# External_Connectors.net
KiCad netlist of a schematic drawn in Altium Designer
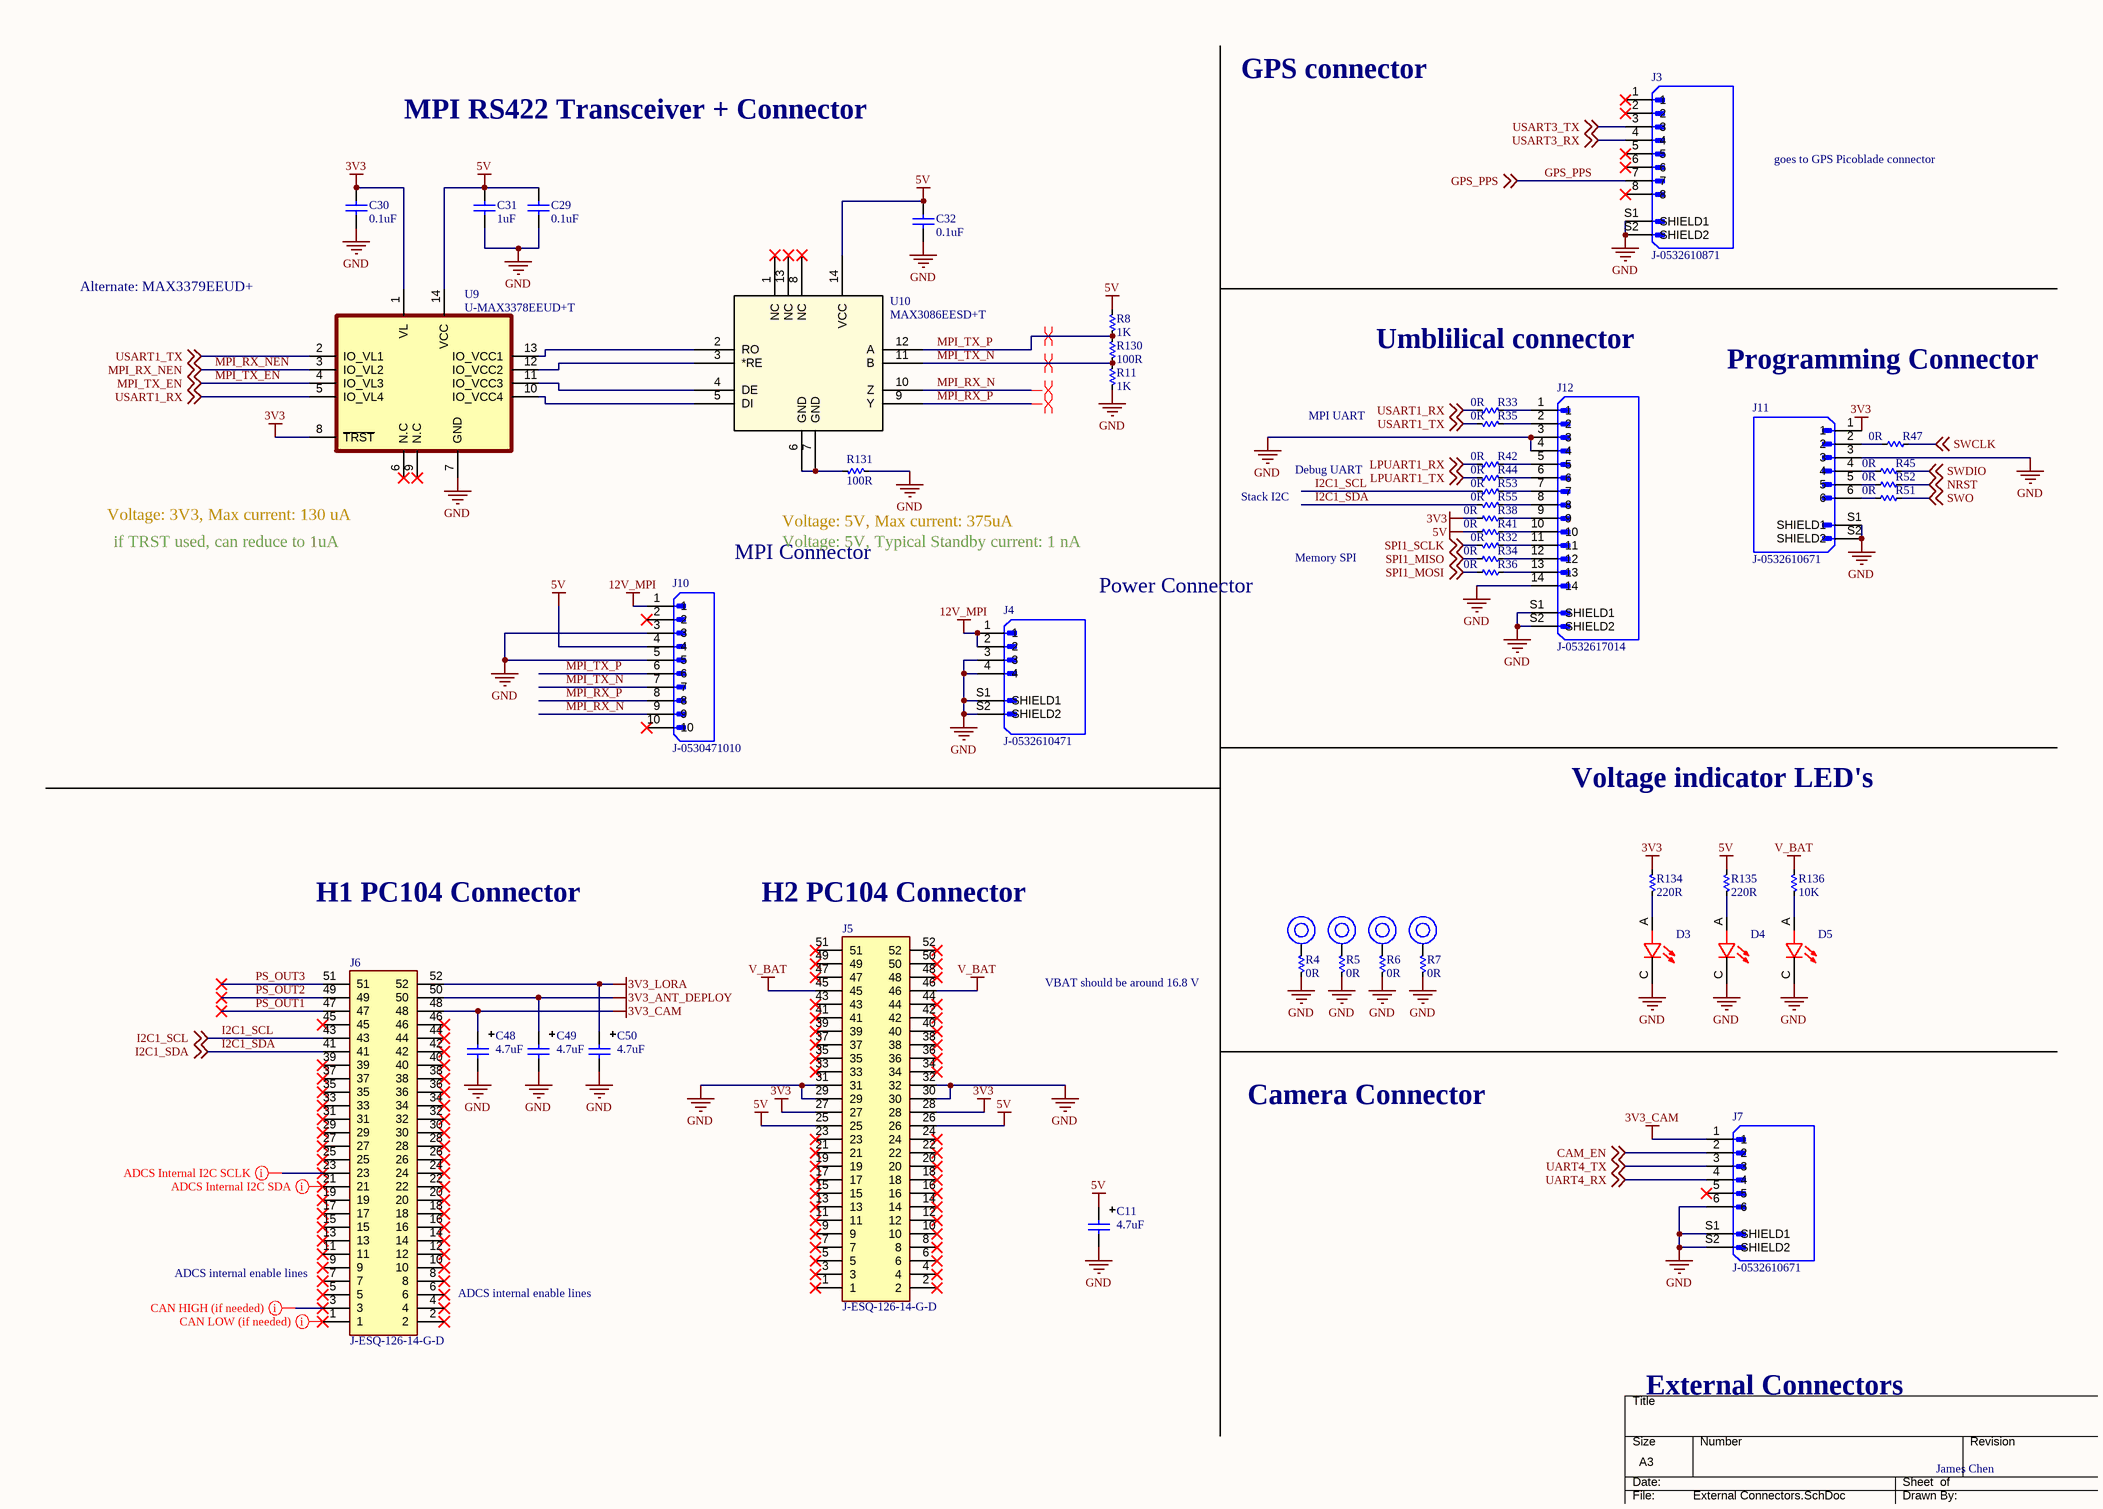
[diagram p0: External Connectors.SchDoc]

(export (version "E")
  (design (tool "Eeschema 10.0.6"))
  (components
    (comp (ref "*1")
      (value "PC104 Mounting")
      (footprint "PC104 Mounting Points")
      (libsource (lib "OBC Development Board") (part "PC104 Mounting"))
    )
    (comp (ref "*2")
      (value "PC104 Mounting")
      (footprint "PC104 Mounting Points")
      (libsource (lib "OBC Development Board") (part "PC104 Mounting"))
    )
    (comp (ref "*3")
      (value "PC104 Mounting")
      (footprint "PC104 Mounting Points")
      (libsource (lib "OBC Development Board") (part "PC104 Mounting"))
    )
    (comp (ref "*4")
      (value "PC104 Mounting")
      (footprint "PC104 Mounting Points")
      (libsource (lib "OBC Development Board") (part "PC104 Mounting"))
    )
    (comp (ref "C11")
      (value "4.7uF")
      (footprint "CAP TANT 1206 (A) TCJ")
      (description "4.7 µF Molded Tantalum Capacitors 20 V 1206 (3216 Metric) 4Ohm")
      (fields
        (field (name "DISTRIBUTOR PART #") "478-1668-1-ND")
        (field (name "MANUFACTURER") "AVX Corporation")
      )
      (libsource (lib "OBC Development Board") (part "CT-474-M-20V-OTH-1206"))
    )
    (comp (ref "C29")
      (value "0.1uF")
      (footprint "0603")
      (description "0.1 µF ±10% 25V Ceramic Capacitor X7R 0603 (1608 Metric)")
      (fields
        (field (name "DISTRIBUTOR PART #") "1276-1006-1-ND")
        (field (name "MANUFACTURER") "Samsung Electro-Mechanics")
      )
      (libsource (lib "OBC Development Board") (part "CC-104-K-25V-X7R-0603"))
    )
    (comp (ref "C30")
      (value "0.1uF")
      (footprint "0603")
      (description "0.1 µF ±10% 25V Ceramic Capacitor X7R 0603 (1608 Metric)")
      (fields
        (field (name "DISTRIBUTOR PART #") "1276-1006-1-ND")
        (field (name "MANUFACTURER") "Samsung Electro-Mechanics")
      )
      (libsource (lib "OBC Development Board") (part "CC-104-K-25V-X7R-0603"))
    )
    (comp (ref "C31")
      (value "1uF")
      (footprint "0603")
      (description "CAP CER 1UF 25V X7R 0603")
      (fields (field (name "DISTRIBUTOR PART #") "311-1802-1-ND") (field (name "MANUFACTURER") "Yageo"))
      (libsource (lib "OBC Development Board") (part "CC-105-K-25V-X7R-0603"))
    )
    (comp (ref "C32")
      (value "0.1uF")
      (footprint "0603")
      (description "0.1 µF ±10% 25V Ceramic Capacitor X7R 0603 (1608 Metric)")
      (fields
        (field (name "DISTRIBUTOR PART #") "1276-1006-1-ND")
        (field (name "MANUFACTURER") "Samsung Electro-Mechanics")
      )
      (libsource (lib "OBC Development Board") (part "CC-104-K-25V-X7R-0603"))
    )
    (comp (ref "C48")
      (value "4.7uF")
      (footprint "CAP TANT 1206 (A) TCJ")
      (description "4.7 µF Molded Tantalum Capacitors 20 V 1206 (3216 Metric) 4Ohm")
      (fields
        (field (name "DISTRIBUTOR PART #") "478-1668-1-ND")
        (field (name "MANUFACTURER") "AVX Corporation")
      )
      (libsource (lib "OBC Development Board") (part "CT-474-M-20V-OTH-1206"))
    )
    (comp (ref "C49")
      (value "4.7uF")
      (footprint "CAP TANT 1206 (A) TCJ")
      (description "4.7 µF Molded Tantalum Capacitors 20 V 1206 (3216 Metric) 4Ohm")
      (fields
        (field (name "DISTRIBUTOR PART #") "478-1668-1-ND")
        (field (name "MANUFACTURER") "AVX Corporation")
      )
      (libsource (lib "OBC Development Board") (part "CT-474-M-20V-OTH-1206"))
    )
    (comp (ref "C50")
      (value "4.7uF")
      (footprint "CAP TANT 1206 (A) TCJ")
      (description "4.7 µF Molded Tantalum Capacitors 20 V 1206 (3216 Metric) 4Ohm")
      (fields
        (field (name "DISTRIBUTOR PART #") "478-1668-1-ND")
        (field (name "MANUFACTURER") "AVX Corporation")
      )
      (libsource (lib "OBC Development Board") (part "CT-474-M-20V-OTH-1206"))
    )
    (comp (ref "D3")
      (value "D-SML-D12U1WT86")
      (footprint "D-SML-D12U1WT86")
      (description "Red 620nm LED Indication - Discrete 2.2V 0603 _1608 Metric")
      (fields
        (field (name "MANUFACTURER PART #") "SML-D12U1WT86")
        (field (name "MANUFACTURER") "Rohm Semiconductor")
      )
      (libsource (lib "OBC Development Board") (part "D-SML-D12U1WT86"))
    )
    (comp (ref "D4")
      (value "D-SML-D12U1WT86")
      (footprint "D-SML-D12U1WT86")
      (description "Red 620nm LED Indication - Discrete 2.2V 0603 _1608 Metric")
      (fields
        (field (name "MANUFACTURER PART #") "SML-D12U1WT86")
        (field (name "MANUFACTURER") "Rohm Semiconductor")
      )
      (libsource (lib "OBC Development Board") (part "D-SML-D12U1WT86"))
    )
    (comp (ref "D5")
      (value "D-SML-D12U1WT86")
      (footprint "D-SML-D12U1WT86")
      (description "Red 620nm LED Indication - Discrete 2.2V 0603 _1608 Metric")
      (fields
        (field (name "MANUFACTURER PART #") "SML-D12U1WT86")
        (field (name "MANUFACTURER") "Rohm Semiconductor")
      )
      (libsource (lib "OBC Development Board") (part "D-SML-D12U1WT86"))
    )
    (comp (ref "J3")
      (value "J-0532610871")
      (footprint "J-532610871")
      (description "CONN HEADER SMD R/A 8POS 1.25MM")
      (fields
        (field (name "MANFACTURER PART #") "0532610871")
        (field (name "DISTRIBUTOR PART #") "WM7626CT-ND")
      )
      (libsource (lib "OBC Development Board") (part "J-0532610871"))
    )
    (comp (ref "J4")
      (value "J-0532610471")
      (footprint "J-53261-0471")
      (description "CONN HEADER SMD R/A 4POS 1.25MM")
      (fields
        (field (name "MANFACTURER PART #") "0532610471")
        (field (name "DISTRIBUTOR PART #") "WM7622CT-ND")
      )
      (libsource (lib "OBC Development Board") (part "J-0532610471"))
    )
    (comp (ref "J5")
      (value "J-ESQ-126-14-G-D")
      (footprint "J-ESQ-126-14-G-D")
      (description "CONN SOCKET 52POS 0.1 GOLD PCB")
      (fields
        (field (name "MANUFACTURER") "Samtec Inc.")
        (field (name "MANUFACTURER PART #") "ESQ-126-14-G-D")
      )
      (libsource (lib "OBC Development Board") (part "J-ESQ-126-14-G-D"))
    )
    (comp (ref "J6")
      (value "J-ESQ-126-14-G-D")
      (footprint "J-ESQ-126-14-G-D")
      (description "CONN SOCKET 52POS 0.1 GOLD PCB")
      (fields
        (field (name "MANUFACTURER") "Samtec Inc.")
        (field (name "MANUFACTURER PART #") "ESQ-126-14-G-D")
      )
      (libsource (lib "OBC Development Board") (part "J-ESQ-126-14-G-D"))
    )
    (comp (ref "J7")
      (value "J-0532610671")
      (footprint "J-0532610671")
      (description "CONN HEADER SMD R/A 6POS 1.25MM")
      (fields
        (field (name "MANFACTURER PART #") "0532610671")
        (field (name "DISTRIBUTOR PART #") "WM7624CT-ND")
      )
      (libsource (lib "") (part "J-0532610671_1"))
    )
    (comp (ref "J10")
      (value "J-0530471010")
      (footprint "J-0530471010")
      (description "CONN HEADER VERT 10POS 1.25MM")
      (fields (field (name "MANUFACTURER") "Molex") (field (name "MANUFACTURER PART #") "0530471010"))
      (libsource (lib "OBC Development Board") (part "J-0530471010"))
    )
    (comp (ref "J11")
      (value "J-0532610671")
      (footprint "J-0532610671")
      (description "CONN HEADER SMD R/A 6POS 1.25MM")
      (fields
        (field (name "MANFACTURER PART #") "0532610671")
        (field (name "DISTRIBUTOR PART #") "WM7624CT-ND")
      )
      (libsource (lib "OBC Development Board") (part "J-0532610671"))
    )
    (comp (ref "J12")
      (value "J-0532617014")
      (footprint "J-532617014")
      (description "Connector Header Surface Mount, Right Angle 14 position 0.049 (1.25mm)")
      (fields (field (name "MANUFACTURER") "Molex") (field (name "MANUFACTURER PART #") "0532617014"))
      (libsource (lib "OBC Development Board") (part "J-0532617014"))
    )
    (comp (ref "R4")
      (value "0R")
      (footprint "0603")
      (description "0 Ohms Jumper 0.1W, 1/10W Chip Resistor 0603 (1608 Metric) Automotive AEC-Q200 Thick Film")
      (fields
        (field (name "DISTRIBUTOR PART #") "RMCF0603ZT0R00CT-ND")
        (field (name "MANUFACTURER") "Stackpole Electronics Inc")
      )
      (libsource (lib "OBC Development Board") (part "RT-0R00-F-1/10W-0603"))
    )
    (comp (ref "R5")
      (value "0R")
      (footprint "0603")
      (description "0 Ohms Jumper 0.1W, 1/10W Chip Resistor 0603 (1608 Metric) Automotive AEC-Q200 Thick Film")
      (fields
        (field (name "DISTRIBUTOR PART #") "RMCF0603ZT0R00CT-ND")
        (field (name "MANUFACTURER") "Stackpole Electronics Inc")
      )
      (libsource (lib "OBC Development Board") (part "RT-0R00-F-1/10W-0603"))
    )
    (comp (ref "R6")
      (value "0R")
      (footprint "0603")
      (description "0 Ohms Jumper 0.1W, 1/10W Chip Resistor 0603 (1608 Metric) Automotive AEC-Q200 Thick Film")
      (fields
        (field (name "DISTRIBUTOR PART #") "RMCF0603ZT0R00CT-ND")
        (field (name "MANUFACTURER") "Stackpole Electronics Inc")
      )
      (libsource (lib "OBC Development Board") (part "RT-0R00-F-1/10W-0603"))
    )
    (comp (ref "R7")
      (value "0R")
      (footprint "0603")
      (description "0 Ohms Jumper 0.1W, 1/10W Chip Resistor 0603 (1608 Metric) Automotive AEC-Q200 Thick Film")
      (fields
        (field (name "DISTRIBUTOR PART #") "RMCF0603ZT0R00CT-ND")
        (field (name "MANUFACTURER") "Stackpole Electronics Inc")
      )
      (libsource (lib "OBC Development Board") (part "RT-0R00-F-1/10W-0603"))
    )
    (comp (ref "R8")
      (value "1K")
      (footprint "0603")
      (description "RES SMD 1K OHM 1% 1/16W 0603")
      (fields
        (field (name "DISTRIBUTOR PART #") "A102226CT-ND")
        (field (name "MANUFACTURER") "TE Connectivity Passive Product")
      )
      (libsource (lib "OBC Development Board") (part "RT-1K0-F-1/16W-0603"))
    )
    (comp (ref "R11")
      (value "1K")
      (footprint "0603")
      (description "RES SMD 1K OHM 1% 1/16W 0603")
      (fields
        (field (name "DISTRIBUTOR PART #") "A102226CT-ND")
        (field (name "MANUFACTURER") "TE Connectivity Passive Product")
      )
      (libsource (lib "OBC Development Board") (part "RT-1K0-F-1/16W-0603"))
    )
    (comp (ref "R32")
      (value "0R")
      (footprint "0603")
      (description "0 Ohms Jumper 0.1W, 1/10W Chip Resistor 0603 (1608 Metric) Automotive AEC-Q200 Thick Film")
      (fields
        (field (name "DISTRIBUTOR PART #") "RMCF0603ZT0R00CT-ND")
        (field (name "MANUFACTURER") "Stackpole Electronics Inc")
      )
      (libsource (lib "OBC Development Board") (part "RT-0R00-F-1/10W-0603"))
    )
    (comp (ref "R33")
      (value "0R")
      (footprint "0603")
      (description "0 Ohms Jumper 0.1W, 1/10W Chip Resistor 0603 (1608 Metric) Automotive AEC-Q200 Thick Film")
      (fields
        (field (name "DISTRIBUTOR PART #") "RMCF0603ZT0R00CT-ND")
        (field (name "MANUFACTURER") "Stackpole Electronics Inc")
      )
      (libsource (lib "OBC Development Board") (part "RT-0R00-F-1/10W-0603"))
    )
    (comp (ref "R34")
      (value "0R")
      (footprint "0603")
      (description "0 Ohms Jumper 0.1W, 1/10W Chip Resistor 0603 (1608 Metric) Automotive AEC-Q200 Thick Film")
      (fields
        (field (name "DISTRIBUTOR PART #") "RMCF0603ZT0R00CT-ND")
        (field (name "MANUFACTURER") "Stackpole Electronics Inc")
      )
      (libsource (lib "OBC Development Board") (part "RT-0R00-F-1/10W-0603"))
    )
    (comp (ref "R35")
      (value "0R")
      (footprint "0603")
      (description "0 Ohms Jumper 0.1W, 1/10W Chip Resistor 0603 (1608 Metric) Automotive AEC-Q200 Thick Film")
      (fields
        (field (name "DISTRIBUTOR PART #") "RMCF0603ZT0R00CT-ND")
        (field (name "MANUFACTURER") "Stackpole Electronics Inc")
      )
      (libsource (lib "OBC Development Board") (part "RT-0R00-F-1/10W-0603"))
    )
    (comp (ref "R36")
      (value "0R")
      (footprint "0603")
      (description "0 Ohms Jumper 0.1W, 1/10W Chip Resistor 0603 (1608 Metric) Automotive AEC-Q200 Thick Film")
      (fields
        (field (name "DISTRIBUTOR PART #") "RMCF0603ZT0R00CT-ND")
        (field (name "MANUFACTURER") "Stackpole Electronics Inc")
      )
      (libsource (lib "OBC Development Board") (part "RT-0R00-F-1/10W-0603"))
    )
    (comp (ref "R38")
      (value "0R")
      (footprint "0603")
      (description "0 Ohms Jumper 0.1W, 1/10W Chip Resistor 0603 (1608 Metric) Automotive AEC-Q200 Thick Film")
      (fields
        (field (name "DISTRIBUTOR PART #") "RMCF0603ZT0R00CT-ND")
        (field (name "MANUFACTURER") "Stackpole Electronics Inc")
      )
      (libsource (lib "OBC Development Board") (part "RT-0R00-F-1/10W-0603"))
    )
    (comp (ref "R41")
      (value "0R")
      (footprint "0603")
      (description "0 Ohms Jumper 0.1W, 1/10W Chip Resistor 0603 (1608 Metric) Automotive AEC-Q200 Thick Film")
      (fields
        (field (name "DISTRIBUTOR PART #") "RMCF0603ZT0R00CT-ND")
        (field (name "MANUFACTURER") "Stackpole Electronics Inc")
      )
      (libsource (lib "OBC Development Board") (part "RT-0R00-F-1/10W-0603"))
    )
    (comp (ref "R42")
      (value "0R")
      (footprint "0603")
      (description "0 Ohms Jumper 0.1W, 1/10W Chip Resistor 0603 (1608 Metric) Automotive AEC-Q200 Thick Film")
      (fields
        (field (name "DISTRIBUTOR PART #") "RMCF0603ZT0R00CT-ND")
        (field (name "MANUFACTURER") "Stackpole Electronics Inc")
      )
      (libsource (lib "OBC Development Board") (part "RT-0R00-F-1/10W-0603"))
    )
    (comp (ref "R44")
      (value "0R")
      (footprint "0603")
      (description "0 Ohms Jumper 0.1W, 1/10W Chip Resistor 0603 (1608 Metric) Automotive AEC-Q200 Thick Film")
      (fields
        (field (name "DISTRIBUTOR PART #") "RMCF0603ZT0R00CT-ND")
        (field (name "MANUFACTURER") "Stackpole Electronics Inc")
      )
      (libsource (lib "OBC Development Board") (part "RT-0R00-F-1/10W-0603"))
    )
    (comp (ref "R45")
      (value "0R")
      (footprint "0603")
      (description "0 Ohms Jumper 0.1W, 1/10W Chip Resistor 0603 (1608 Metric) Automotive AEC-Q200 Thick Film")
      (fields
        (field (name "DISTRIBUTOR PART #") "RMCF0603ZT0R00CT-ND")
        (field (name "MANUFACTURER") "Stackpole Electronics Inc")
      )
      (libsource (lib "OBC Development Board") (part "RT-0R00-F-1/10W-0603"))
    )
    (comp (ref "R47")
      (value "0R")
      (footprint "0603")
      (description "0 Ohms Jumper 0.1W, 1/10W Chip Resistor 0603 (1608 Metric) Automotive AEC-Q200 Thick Film")
      (fields
        (field (name "DISTRIBUTOR PART #") "RMCF0603ZT0R00CT-ND")
        (field (name "MANUFACTURER") "Stackpole Electronics Inc")
      )
      (libsource (lib "OBC Development Board") (part "RT-0R00-F-1/10W-0603"))
    )
    (comp (ref "R51")
      (value "0R")
      (footprint "0603")
      (description "0 Ohms Jumper 0.1W, 1/10W Chip Resistor 0603 (1608 Metric) Automotive AEC-Q200 Thick Film")
      (fields
        (field (name "DISTRIBUTOR PART #") "RMCF0603ZT0R00CT-ND")
        (field (name "MANUFACTURER") "Stackpole Electronics Inc")
      )
      (libsource (lib "OBC Development Board") (part "RT-0R00-F-1/10W-0603"))
    )
    (comp (ref "R52")
      (value "0R")
      (footprint "0603")
      (description "0 Ohms Jumper 0.1W, 1/10W Chip Resistor 0603 (1608 Metric) Automotive AEC-Q200 Thick Film")
      (fields
        (field (name "DISTRIBUTOR PART #") "RMCF0603ZT0R00CT-ND")
        (field (name "MANUFACTURER") "Stackpole Electronics Inc")
      )
      (libsource (lib "OBC Development Board") (part "RT-0R00-F-1/10W-0603"))
    )
    (comp (ref "R53")
      (value "0R")
      (footprint "0603")
      (description "0 Ohms Jumper 0.1W, 1/10W Chip Resistor 0603 (1608 Metric) Automotive AEC-Q200 Thick Film")
      (fields
        (field (name "DISTRIBUTOR PART #") "RMCF0603ZT0R00CT-ND")
        (field (name "MANUFACTURER") "Stackpole Electronics Inc")
      )
      (libsource (lib "OBC Development Board") (part "RT-0R00-F-1/10W-0603"))
    )
    (comp (ref "R55")
      (value "0R")
      (footprint "0603")
      (description "0 Ohms Jumper 0.1W, 1/10W Chip Resistor 0603 (1608 Metric) Automotive AEC-Q200 Thick Film")
      (fields
        (field (name "DISTRIBUTOR PART #") "RMCF0603ZT0R00CT-ND")
        (field (name "MANUFACTURER") "Stackpole Electronics Inc")
      )
      (libsource (lib "OBC Development Board") (part "RT-0R00-F-1/10W-0603"))
    )
    (comp (ref "R130")
      (value "100R")
      (footprint "0603")
      (description "RES SMD 100 OHM 0.5% 1/16W 0603")
      (fields (field (name "DISTRIBUTOR PART #") "RR08P100DCT-ND") (field (name "MANUFACTURER") "Susumu"))
      (libsource (lib "OBC Development Board") (part "RT-100R-F-1/16W-0603"))
    )
    (comp (ref "R131")
      (value "100R")
      (footprint "0603")
      (description "RES SMD 100 OHM 0.5% 1/16W 0603")
      (fields (field (name "DISTRIBUTOR PART #") "RR08P100DCT-ND") (field (name "MANUFACTURER") "Susumu"))
      (libsource (lib "OBC Development Board") (part "RT-100R-F-1/16W-0603"))
    )
    (comp (ref "R134")
      (value "220R")
      (footprint "0402")
      (description "RES 220 OHM 5% 1/16W 0402")
      (fields (field (name "DISTRIBUTOR PART #") "311-220JRCT-ND") (field (name "MANUFACTURER") "Yageo"))
      (libsource (lib "OBC Development Board") (part "RT-220R-F-1/16W-0402"))
    )
    (comp (ref "R135")
      (value "220R")
      (footprint "0402")
      (description "RES 220 OHM 5% 1/16W 0402")
      (fields (field (name "DISTRIBUTOR PART #") "311-220JRCT-ND") (field (name "MANUFACTURER") "Yageo"))
      (libsource (lib "OBC Development Board") (part "RT-220R-F-1/16W-0402"))
    )
    (comp (ref "R136")
      (value "10K")
      (footprint "0603")
      (description "10 kOhms ±0.1% 0.063W, 1/16W Chip Resistor 0603 (1608 Metric) - Thin Film")
      (fields
        (field (name "DISTRIBUTOR PART #") "A119886CT-ND")
        (field (name "MANUFACTURER") "TE Connectivity Passive Product")
      )
      (libsource (lib "OBC Development Board") (part "RT-10K0-F-1/16W-0603"))
    )
    (comp (ref "U9")
      (value "U-MAX3378EEUD+T")
      (footprint "OBC Development Board:U-MAX3378EEUD+T")
      (description "IC TRNSLTR BIDIRECTIONAL 14TSSOP")
      (fields
        (field (name "MANUFACTURER PART #") "MAX3378EEUD+T")
        (field (name "MANUFACTURER") "Maxim Integrated")
      )
      (libsource (lib "OBC Development Board") (part "U-MAX3378EEUD+T"))
    )
    (comp (ref "U10")
      (value "MAX3086EESD+T")
      (footprint "U-MAX3086EESD+T")
      (description "IC TRANSCEIVER FULL 1/1 14SOIC")
      (fields
        (field (name "MANUFACTURER") "Maxim Integrated Products")
        (field (name "DISTRIBUTOR PART #") "MAX3086EESD+TCT-ND")
      )
      (libsource (lib "OBC Development Board") (part "U-MAX3086EESD+T"))
    )
  )
  (nets
    (net (code "1") (name "/MPI_RX_N") (class "Default")
      (node (ref "J10") (pin "9") (pinfunction "9_9") (pintype "passive"))
      (node (ref "U10") (pin "10") (pinfunction "Z_10") (pintype "passive"))
    )
    (net (code "2") (name "/MPI_RX_P") (class "Default")
      (node (ref "J10") (pin "8") (pinfunction "8_8") (pintype "passive"))
      (node (ref "U10") (pin "9") (pinfunction "Y_9") (pintype "passive"))
    )
    (net (code "3") (name "/MPI_TX_N") (class "Default")
      (node (ref "J10") (pin "7") (pinfunction "7_7") (pintype "passive"))
      (node (ref "R11") (pin "2") (pintype "passive"))
      (node (ref "R130") (pin "1") (pintype "passive"))
      (node (ref "U10") (pin "11") (pinfunction "B_11") (pintype "passive"))
    )
    (net (code "4") (name "/MPI_TX_P") (class "Default")
      (node (ref "J10") (pin "6") (pinfunction "6_6") (pintype "passive"))
      (node (ref "R130") (pin "2") (pintype "passive"))
      (node (ref "R8") (pin "1") (pintype "passive"))
      (node (ref "U10") (pin "12") (pinfunction "A_12") (pintype "passive"))
    )
    (net (code "5") (name "/PS_OUT1") (class "Default")
      (node (ref "J6") (pin "47") (pinfunction "47_47") (pintype "passive+no_connect"))
    )
    (net (code "6") (name "/PS_OUT2") (class "Default")
      (node (ref "J6") (pin "49") (pinfunction "49_49") (pintype "passive+no_connect"))
    )
    (net (code "7") (name "/PS_OUT3") (class "Default")
      (node (ref "J6") (pin "51") (pinfunction "51_51") (pintype "passive+no_connect"))
    )
    (net (code "8") (name "3V3") (class "Default")
      (node (ref "C30") (pin "1") (pinfunction "1_1") (pintype "passive"))
      (node (ref "J11") (pin "1") (pinfunction "1_1") (pintype "passive"))
      (node (ref "J5") (pin "27") (pinfunction "27_27") (pintype "passive"))
      (node (ref "J5") (pin "28") (pinfunction "28_28") (pintype "passive"))
      (node (ref "R134") (pin "1") (pintype "passive"))
      (node (ref "R38") (pin "2") (pintype "passive"))
      (node (ref "U9") (pin "1") (pinfunction "VL_1") (pintype "power_in"))
      (node (ref "U9") (pin "8") (pinfunction "~{TRST}_8") (pintype "passive"))
    )
    (net (code "9") (name "3V3_ANT_DEPLOY") (class "Default")
      (node (ref "C49") (pin "1") (pinfunction "1_1") (pintype "passive"))
      (node (ref "J6") (pin "50") (pinfunction "50_50") (pintype "passive"))
    )
    (net (code "10") (name "3V3_CAM") (class "Default")
      (node (ref "C48") (pin "1") (pinfunction "1_1") (pintype "passive"))
      (node (ref "J6") (pin "48") (pinfunction "48_48") (pintype "passive"))
      (node (ref "J7") (pin "1") (pinfunction "1_1") (pintype "passive"))
    )
    (net (code "11") (name "3V3_LORA") (class "Default")
      (node (ref "C50") (pin "1") (pinfunction "1_1") (pintype "passive"))
      (node (ref "J6") (pin "52") (pinfunction "52_52") (pintype "passive"))
    )
    (net (code "12") (name "5V") (class "Default")
      (node (ref "C11") (pin "1") (pinfunction "1_1") (pintype "passive"))
      (node (ref "C29") (pin "1") (pinfunction "1_1") (pintype "passive"))
      (node (ref "C31") (pin "2") (pinfunction "2_2") (pintype "passive"))
      (node (ref "C32") (pin "1") (pinfunction "1_1") (pintype "passive"))
      (node (ref "J10") (pin "4") (pinfunction "4_4") (pintype "passive"))
      (node (ref "J5") (pin "25") (pinfunction "25_25") (pintype "passive"))
      (node (ref "J5") (pin "26") (pinfunction "26_26") (pintype "passive"))
      (node (ref "R135") (pin "1") (pintype "passive"))
      (node (ref "R41") (pin "2") (pintype "passive"))
      (node (ref "R8") (pin "2") (pintype "passive"))
      (node (ref "U10") (pin "14") (pinfunction "VCC_14") (pintype "power_in"))
      (node (ref "U9") (pin "14") (pinfunction "VCC_14") (pintype "power_in"))
    )
    (net (code "13") (name "12V_MPI") (class "Default")
      (node (ref "J10") (pin "1") (pinfunction "1_1") (pintype "passive"))
      (node (ref "J4") (pin "1") (pinfunction "1_1") (pintype "passive"))
      (node (ref "J4") (pin "2") (pinfunction "2_2") (pintype "passive"))
    )
    (net (code "14") (name "CAM_EN") (class "Default")
      (node (ref "J7") (pin "2") (pinfunction "2_2") (pintype "passive"))
    )
    (net (code "15") (name "GND") (class "Default")
      (node (ref "C11") (pin "2") (pinfunction "2_2") (pintype "passive"))
      (node (ref "C29") (pin "2") (pinfunction "2_2") (pintype "passive"))
      (node (ref "C30") (pin "2") (pinfunction "2_2") (pintype "passive"))
      (node (ref "C31") (pin "1") (pinfunction "1_1") (pintype "passive"))
      (node (ref "C32") (pin "2") (pinfunction "2_2") (pintype "passive"))
      (node (ref "C48") (pin "2") (pinfunction "2_2") (pintype "passive"))
      (node (ref "C49") (pin "2") (pinfunction "2_2") (pintype "passive"))
      (node (ref "C50") (pin "2") (pinfunction "2_2") (pintype "passive"))
      (node (ref "D3") (pin "C") (pinfunction "C_C") (pintype "passive"))
      (node (ref "D4") (pin "C") (pinfunction "C_C") (pintype "passive"))
      (node (ref "D5") (pin "C") (pinfunction "C_C") (pintype "passive"))
      (node (ref "J10") (pin "3") (pinfunction "3_3") (pintype "passive"))
      (node (ref "J10") (pin "5") (pinfunction "5_5") (pintype "passive"))
      (node (ref "J11") (pin "3") (pinfunction "3_3") (pintype "passive"))
      (node (ref "J11") (pin "S1") (pinfunction "SHIELD1_S1") (pintype "passive"))
      (node (ref "J11") (pin "S2") (pinfunction "SHIELD2_S2") (pintype "passive"))
      (node (ref "J12") (pin "14") (pinfunction "14_14") (pintype "passive"))
      (node (ref "J12") (pin "3") (pinfunction "3_3") (pintype "passive"))
      (node (ref "J12") (pin "4") (pinfunction "4_4") (pintype "passive"))
      (node (ref "J12") (pin "S1") (pinfunction "SHIELD1_S1") (pintype "passive"))
      (node (ref "J12") (pin "S2") (pinfunction "SHIELD2_S2") (pintype "passive"))
      (node (ref "J3") (pin "S1") (pinfunction "SHIELD1_S1") (pintype "passive"))
      (node (ref "J3") (pin "S2") (pinfunction "SHIELD2_S2") (pintype "passive"))
      (node (ref "J4") (pin "3") (pinfunction "3_3") (pintype "passive"))
      (node (ref "J4") (pin "4") (pinfunction "4_4") (pintype "passive"))
      (node (ref "J4") (pin "S1") (pinfunction "SHIELD1_S1") (pintype "passive"))
      (node (ref "J4") (pin "S2") (pinfunction "SHIELD2_S2") (pintype "passive"))
      (node (ref "J5") (pin "29") (pinfunction "29_29") (pintype "passive"))
      (node (ref "J5") (pin "30") (pinfunction "30_30") (pintype "passive"))
      (node (ref "J5") (pin "31") (pinfunction "31_31") (pintype "passive"))
      (node (ref "J5") (pin "32") (pinfunction "32_32") (pintype "passive"))
      (node (ref "J7") (pin "6") (pinfunction "6_6") (pintype "passive"))
      (node (ref "J7") (pin "S1") (pinfunction "SHIELD1_S1") (pintype "passive"))
      (node (ref "J7") (pin "S2") (pinfunction "SHIELD2_S2") (pintype "passive"))
      (node (ref "R11") (pin "1") (pintype "passive"))
      (node (ref "R131") (pin "1") (pintype "passive"))
      (node (ref "R4") (pin "1") (pintype "passive"))
      (node (ref "R5") (pin "1") (pintype "passive"))
      (node (ref "R6") (pin "1") (pintype "passive"))
      (node (ref "R7") (pin "1") (pintype "passive"))
      (node (ref "U9") (pin "7") (pinfunction "GND_7") (pintype "passive"))
    )
    (net (code "16") (name "GPS_PPS") (class "Default")
      (node (ref "J3") (pin "7") (pinfunction "7_7") (pintype "passive"))
    )
    (net (code "17") (name "I2C1_SCL") (class "Default")
      (node (ref "J6") (pin "43") (pinfunction "43_43") (pintype "passive"))
      (node (ref "R53") (pin "1") (pintype "passive"))
    )
    (net (code "18") (name "I2C1_SDA") (class "Default")
      (node (ref "J6") (pin "41") (pinfunction "41_41") (pintype "passive"))
      (node (ref "R55") (pin "1") (pintype "passive"))
    )
    (net (code "19") (name "LPUART1_RX") (class "Default") (node (ref "R42") (pin "1") (pintype "passive")))
    (net (code "20") (name "LPUART1_TX") (class "Default") (node (ref "R44") (pin "1") (pintype "passive")))
    (net (code "21") (name "MPI_RX_NEN") (class "Default")
      (node (ref "U9") (pin "3") (pinfunction "IO_VL2_3") (pintype "passive"))
    )
    (net (code "22") (name "MPI_TX_EN") (class "Default")
      (node (ref "U9") (pin "4") (pinfunction "IO_VL3_4") (pintype "passive"))
    )
    (net (code "23") (name "NRST") (class "Default") (node (ref "R52") (pin "1") (pintype "passive")))
    (net (code "24") (name "Net-(*1-Pad1)") (class "Default")
      (node (ref "*1") (pin "1") (pintype "passive"))
      (node (ref "R4") (pin "2") (pintype "passive"))
    )
    (net (code "25") (name "Net-(*2-Pad1)") (class "Default")
      (node (ref "*2") (pin "1") (pintype "passive"))
      (node (ref "R5") (pin "2") (pintype "passive"))
    )
    (net (code "26") (name "Net-(*3-Pad1)") (class "Default")
      (node (ref "*3") (pin "1") (pintype "passive"))
      (node (ref "R6") (pin "2") (pintype "passive"))
    )
    (net (code "27") (name "Net-(*4-Pad1)") (class "Default")
      (node (ref "*4") (pin "1") (pintype "passive"))
      (node (ref "R7") (pin "2") (pintype "passive"))
    )
    (net (code "28") (name "Net-(D3-PadA)") (class "Default")
      (node (ref "D3") (pin "A") (pinfunction "A_A") (pintype "passive"))
      (node (ref "R134") (pin "2") (pintype "passive"))
    )
    (net (code "29") (name "Net-(D4-PadA)") (class "Default")
      (node (ref "D4") (pin "A") (pinfunction "A_A") (pintype "passive"))
      (node (ref "R135") (pin "2") (pintype "passive"))
    )
    (net (code "30") (name "Net-(D5-PadA)") (class "Default")
      (node (ref "D5") (pin "A") (pinfunction "A_A") (pintype "passive"))
      (node (ref "R136") (pin "1") (pintype "passive"))
    )
    (net (code "31") (name "Net-(J11-Pad2)") (class "Default")
      (node (ref "J11") (pin "2") (pinfunction "2_2") (pintype "passive"))
      (node (ref "R47") (pin "2") (pintype "passive"))
    )
    (net (code "32") (name "Net-(J11-Pad4)") (class "Default")
      (node (ref "J11") (pin "4") (pinfunction "4_4") (pintype "passive"))
      (node (ref "R45") (pin "2") (pintype "passive"))
    )
    (net (code "33") (name "Net-(J11-Pad5)") (class "Default")
      (node (ref "J11") (pin "5") (pinfunction "5_5") (pintype "passive"))
      (node (ref "R52") (pin "2") (pintype "passive"))
    )
    (net (code "34") (name "Net-(J11-Pad6)") (class "Default")
      (node (ref "J11") (pin "6") (pinfunction "6_6") (pintype "passive"))
      (node (ref "R51") (pin "2") (pintype "passive"))
    )
    (net (code "35") (name "Net-(J12-Pad1)") (class "Default")
      (node (ref "J12") (pin "1") (pinfunction "1_1") (pintype "passive"))
      (node (ref "R33") (pin "2") (pintype "passive"))
    )
    (net (code "36") (name "Net-(J12-Pad2)") (class "Default")
      (node (ref "J12") (pin "2") (pinfunction "2_2") (pintype "passive"))
      (node (ref "R35") (pin "2") (pintype "passive"))
    )
    (net (code "37") (name "Net-(J12-Pad5)") (class "Default")
      (node (ref "J12") (pin "5") (pinfunction "5_5") (pintype "passive"))
      (node (ref "R42") (pin "2") (pintype "passive"))
    )
    (net (code "38") (name "Net-(J12-Pad6)") (class "Default")
      (node (ref "J12") (pin "6") (pinfunction "6_6") (pintype "passive"))
      (node (ref "R44") (pin "2") (pintype "passive"))
    )
    (net (code "39") (name "Net-(J12-Pad7)") (class "Default")
      (node (ref "J12") (pin "7") (pinfunction "7_7") (pintype "passive"))
      (node (ref "R53") (pin "2") (pintype "passive"))
    )
    (net (code "40") (name "Net-(J12-Pad8)") (class "Default")
      (node (ref "J12") (pin "8") (pinfunction "8_8") (pintype "passive"))
      (node (ref "R55") (pin "2") (pintype "passive"))
    )
    (net (code "41") (name "Net-(J12-Pad9)") (class "Default")
      (node (ref "J12") (pin "9") (pinfunction "9_9") (pintype "passive"))
      (node (ref "R38") (pin "1") (pintype "passive"))
    )
    (net (code "42") (name "Net-(J12-Pad10)") (class "Default")
      (node (ref "J12") (pin "10") (pinfunction "10_10") (pintype "passive"))
      (node (ref "R41") (pin "1") (pintype "passive"))
    )
    (net (code "43") (name "Net-(J12-Pad11)") (class "Default")
      (node (ref "J12") (pin "11") (pinfunction "11_11") (pintype "passive"))
      (node (ref "R32") (pin "2") (pintype "passive"))
    )
    (net (code "44") (name "Net-(J12-Pad12)") (class "Default")
      (node (ref "J12") (pin "12") (pinfunction "12_12") (pintype "passive"))
      (node (ref "R34") (pin "1") (pintype "passive"))
    )
    (net (code "45") (name "Net-(J12-Pad13)") (class "Default")
      (node (ref "J12") (pin "13") (pinfunction "13_13") (pintype "passive"))
      (node (ref "R36") (pin "1") (pintype "passive"))
    )
    (net (code "46") (name "Net-(R131-Pad2)") (class "Default")
      (node (ref "R131") (pin "2") (pintype "passive"))
      (node (ref "U10") (pin "6") (pinfunction "GND_6") (pintype "power_in"))
      (node (ref "U10") (pin "7") (pinfunction "GND_7") (pintype "power_in"))
    )
    (net (code "47") (name "Net-(U10-*RE)") (class "Default")
      (node (ref "U10") (pin "3") (pinfunction "*RE_3") (pintype "passive"))
      (node (ref "U9") (pin "12") (pinfunction "IO_VCC2_12") (pintype "passive"))
    )
    (net (code "48") (name "Net-(U10-DE)") (class "Default")
      (node (ref "U10") (pin "4") (pinfunction "DE_4") (pintype "passive"))
      (node (ref "U9") (pin "11") (pinfunction "IO_VCC3_11") (pintype "passive"))
    )
    (net (code "49") (name "Net-(U10-DI)") (class "Default")
      (node (ref "U10") (pin "5") (pinfunction "DI_5") (pintype "passive"))
      (node (ref "U9") (pin "10") (pinfunction "IO_VCC4_10") (pintype "passive"))
    )
    (net (code "50") (name "Net-(U10-RO)") (class "Default")
      (node (ref "U10") (pin "2") (pinfunction "RO_2") (pintype "passive"))
      (node (ref "U9") (pin "13") (pinfunction "IO_VCC1_13") (pintype "passive"))
    )
    (net (code "51") (name "SPI1_MISO") (class "Default") (node (ref "R34") (pin "2") (pintype "passive")))
    (net (code "52") (name "SPI1_MOSI") (class "Default") (node (ref "R36") (pin "2") (pintype "passive")))
    (net (code "53") (name "SPI1_SCLK") (class "Default") (node (ref "R32") (pin "1") (pintype "passive")))
    (net (code "54") (name "SWCLK") (class "Default") (node (ref "R47") (pin "1") (pintype "passive")))
    (net (code "55") (name "SWDIO") (class "Default") (node (ref "R45") (pin "1") (pintype "passive")))
    (net (code "56") (name "SWO") (class "Default") (node (ref "R51") (pin "1") (pintype "passive")))
    (net (code "57") (name "UART4_RX") (class "Default")
      (node (ref "J7") (pin "4") (pinfunction "4_4") (pintype "passive"))
    )
    (net (code "58") (name "UART4_TX") (class "Default")
      (node (ref "J7") (pin "3") (pinfunction "3_3") (pintype "passive"))
    )
    (net (code "59") (name "USART1_RX") (class "Default")
      (node (ref "R33") (pin "1") (pintype "passive"))
      (node (ref "U9") (pin "5") (pinfunction "IO_VL4_5") (pintype "passive"))
    )
    (net (code "60") (name "USART1_TX") (class "Default")
      (node (ref "R35") (pin "1") (pintype "passive"))
      (node (ref "U9") (pin "2") (pinfunction "IO_VL1_2") (pintype "passive"))
    )
    (net (code "61") (name "USART3_RX") (class "Default")
      (node (ref "J3") (pin "4") (pinfunction "4_4") (pintype "passive"))
    )
    (net (code "62") (name "USART3_TX") (class "Default")
      (node (ref "J3") (pin "3") (pinfunction "3_3") (pintype "passive"))
    )
    (net (code "63") (name "V_BAT") (class "Default")
      (node (ref "J5") (pin "45") (pinfunction "45_45") (pintype "passive"))
      (node (ref "J5") (pin "46") (pinfunction "46_46") (pintype "passive"))
      (node (ref "R136") (pin "2") (pintype "passive"))
    )
    (net (code "64") (name "unconnected-(J3-Pad1)") (class "Default")
      (node (ref "J3") (pin "1") (pinfunction "1_1") (pintype "passive+no_connect"))
    )
    (net (code "65") (name "unconnected-(J3-Pad2)") (class "Default")
      (node (ref "J3") (pin "2") (pinfunction "2_2") (pintype "passive+no_connect"))
    )
    (net (code "66") (name "unconnected-(J3-Pad5)") (class "Default")
      (node (ref "J3") (pin "5") (pinfunction "5_5") (pintype "passive+no_connect"))
    )
    (net (code "67") (name "unconnected-(J3-Pad6)") (class "Default")
      (node (ref "J3") (pin "6") (pinfunction "6_6") (pintype "passive+no_connect"))
    )
    (net (code "68") (name "unconnected-(J3-Pad8)") (class "Default")
      (node (ref "J3") (pin "8") (pinfunction "8_8") (pintype "passive+no_connect"))
    )
    (net (code "69") (name "unconnected-(J5-Pad1)") (class "Default")
      (node (ref "J5") (pin "1") (pinfunction "1_1") (pintype "passive+no_connect"))
    )
    (net (code "70") (name "unconnected-(J5-Pad2)") (class "Default")
      (node (ref "J5") (pin "2") (pinfunction "2_2") (pintype "passive+no_connect"))
    )
    (net (code "71") (name "unconnected-(J5-Pad3)") (class "Default")
      (node (ref "J5") (pin "3") (pinfunction "3_3") (pintype "passive+no_connect"))
    )
    (net (code "72") (name "unconnected-(J5-Pad4)") (class "Default")
      (node (ref "J5") (pin "4") (pinfunction "4_4") (pintype "passive+no_connect"))
    )
    (net (code "73") (name "unconnected-(J5-Pad5)") (class "Default")
      (node (ref "J5") (pin "5") (pinfunction "5_5") (pintype "passive+no_connect"))
    )
    (net (code "74") (name "unconnected-(J5-Pad6)") (class "Default")
      (node (ref "J5") (pin "6") (pinfunction "6_6") (pintype "passive+no_connect"))
    )
    (net (code "75") (name "unconnected-(J5-Pad7)") (class "Default")
      (node (ref "J5") (pin "7") (pinfunction "7_7") (pintype "passive+no_connect"))
    )
    (net (code "76") (name "unconnected-(J5-Pad8)") (class "Default")
      (node (ref "J5") (pin "8") (pinfunction "8_8") (pintype "passive+no_connect"))
    )
    (net (code "77") (name "unconnected-(J5-Pad9)") (class "Default")
      (node (ref "J5") (pin "9") (pinfunction "9_9") (pintype "passive+no_connect"))
    )
    (net (code "78") (name "unconnected-(J5-Pad10)") (class "Default")
      (node (ref "J5") (pin "10") (pinfunction "10_10") (pintype "passive+no_connect"))
    )
    (net (code "79") (name "unconnected-(J5-Pad11)") (class "Default")
      (node (ref "J5") (pin "11") (pinfunction "11_11") (pintype "passive+no_connect"))
    )
    (net (code "80") (name "unconnected-(J5-Pad12)") (class "Default")
      (node (ref "J5") (pin "12") (pinfunction "12_12") (pintype "passive+no_connect"))
    )
    (net (code "81") (name "unconnected-(J5-Pad13)") (class "Default")
      (node (ref "J5") (pin "13") (pinfunction "13_13") (pintype "passive+no_connect"))
    )
    (net (code "82") (name "unconnected-(J5-Pad14)") (class "Default")
      (node (ref "J5") (pin "14") (pinfunction "14_14") (pintype "passive+no_connect"))
    )
    (net (code "83") (name "unconnected-(J5-Pad15)") (class "Default")
      (node (ref "J5") (pin "15") (pinfunction "15_15") (pintype "passive+no_connect"))
    )
    (net (code "84") (name "unconnected-(J5-Pad16)") (class "Default")
      (node (ref "J5") (pin "16") (pinfunction "16_16") (pintype "passive+no_connect"))
    )
    (net (code "85") (name "unconnected-(J5-Pad17)") (class "Default")
      (node (ref "J5") (pin "17") (pinfunction "17_17") (pintype "passive+no_connect"))
    )
    (net (code "86") (name "unconnected-(J5-Pad18)") (class "Default")
      (node (ref "J5") (pin "18") (pinfunction "18_18") (pintype "passive+no_connect"))
    )
    (net (code "87") (name "unconnected-(J5-Pad19)") (class "Default")
      (node (ref "J5") (pin "19") (pinfunction "19_19") (pintype "passive+no_connect"))
    )
    (net (code "88") (name "unconnected-(J5-Pad20)") (class "Default")
      (node (ref "J5") (pin "20") (pinfunction "20_20") (pintype "passive+no_connect"))
    )
    (net (code "89") (name "unconnected-(J5-Pad21)") (class "Default")
      (node (ref "J5") (pin "21") (pinfunction "21_21") (pintype "passive+no_connect"))
    )
    (net (code "90") (name "unconnected-(J5-Pad22)") (class "Default")
      (node (ref "J5") (pin "22") (pinfunction "22_22") (pintype "passive+no_connect"))
    )
    (net (code "91") (name "unconnected-(J5-Pad23)") (class "Default")
      (node (ref "J5") (pin "23") (pinfunction "23_23") (pintype "passive+no_connect"))
    )
    (net (code "92") (name "unconnected-(J5-Pad24)") (class "Default")
      (node (ref "J5") (pin "24") (pinfunction "24_24") (pintype "passive+no_connect"))
    )
    (net (code "93") (name "unconnected-(J5-Pad33)") (class "Default")
      (node (ref "J5") (pin "33") (pinfunction "33_33") (pintype "passive+no_connect"))
    )
    (net (code "94") (name "unconnected-(J5-Pad34)") (class "Default")
      (node (ref "J5") (pin "34") (pinfunction "34_34") (pintype "passive+no_connect"))
    )
    (net (code "95") (name "unconnected-(J5-Pad35)") (class "Default")
      (node (ref "J5") (pin "35") (pinfunction "35_35") (pintype "passive+no_connect"))
    )
    (net (code "96") (name "unconnected-(J5-Pad36)") (class "Default")
      (node (ref "J5") (pin "36") (pinfunction "36_36") (pintype "passive+no_connect"))
    )
    (net (code "97") (name "unconnected-(J5-Pad37)") (class "Default")
      (node (ref "J5") (pin "37") (pinfunction "37_37") (pintype "passive+no_connect"))
    )
    (net (code "98") (name "unconnected-(J5-Pad38)") (class "Default")
      (node (ref "J5") (pin "38") (pinfunction "38_38") (pintype "passive+no_connect"))
    )
    (net (code "99") (name "unconnected-(J5-Pad39)") (class "Default")
      (node (ref "J5") (pin "39") (pinfunction "39_39") (pintype "passive+no_connect"))
    )
    (net (code "100") (name "unconnected-(J5-Pad40)") (class "Default")
      (node (ref "J5") (pin "40") (pinfunction "40_40") (pintype "passive+no_connect"))
    )
    (net (code "101") (name "unconnected-(J5-Pad41)") (class "Default")
      (node (ref "J5") (pin "41") (pinfunction "41_41") (pintype "passive+no_connect"))
    )
    (net (code "102") (name "unconnected-(J5-Pad42)") (class "Default")
      (node (ref "J5") (pin "42") (pinfunction "42_42") (pintype "passive+no_connect"))
    )
    (net (code "103") (name "unconnected-(J5-Pad43)") (class "Default")
      (node (ref "J5") (pin "43") (pinfunction "43_43") (pintype "passive+no_connect"))
    )
    (net (code "104") (name "unconnected-(J5-Pad44)") (class "Default")
      (node (ref "J5") (pin "44") (pinfunction "44_44") (pintype "passive+no_connect"))
    )
    (net (code "105") (name "unconnected-(J5-Pad47)") (class "Default")
      (node (ref "J5") (pin "47") (pinfunction "47_47") (pintype "passive+no_connect"))
    )
    (net (code "106") (name "unconnected-(J5-Pad48)") (class "Default")
      (node (ref "J5") (pin "48") (pinfunction "48_48") (pintype "passive+no_connect"))
    )
    (net (code "107") (name "unconnected-(J5-Pad49)") (class "Default")
      (node (ref "J5") (pin "49") (pinfunction "49_49") (pintype "passive+no_connect"))
    )
    (net (code "108") (name "unconnected-(J5-Pad50)") (class "Default")
      (node (ref "J5") (pin "50") (pinfunction "50_50") (pintype "passive+no_connect"))
    )
    (net (code "109") (name "unconnected-(J5-Pad51)") (class "Default")
      (node (ref "J5") (pin "51") (pinfunction "51_51") (pintype "passive+no_connect"))
    )
    (net (code "110") (name "unconnected-(J5-Pad52)") (class "Default")
      (node (ref "J5") (pin "52") (pinfunction "52_52") (pintype "passive+no_connect"))
    )
    (net (code "111") (name "unconnected-(J6-Pad1)") (class "Default")
      (node (ref "J6") (pin "1") (pinfunction "1_1") (pintype "passive+no_connect"))
    )
    (net (code "112") (name "unconnected-(J6-Pad2)") (class "Default")
      (node (ref "J6") (pin "2") (pinfunction "2_2") (pintype "passive+no_connect"))
    )
    (net (code "113") (name "unconnected-(J6-Pad3)") (class "Default")
      (node (ref "J6") (pin "3") (pinfunction "3_3") (pintype "passive+no_connect"))
    )
    (net (code "114") (name "unconnected-(J6-Pad4)") (class "Default")
      (node (ref "J6") (pin "4") (pinfunction "4_4") (pintype "passive+no_connect"))
    )
    (net (code "115") (name "unconnected-(J6-Pad5)") (class "Default")
      (node (ref "J6") (pin "5") (pinfunction "5_5") (pintype "passive+no_connect"))
    )
    (net (code "116") (name "unconnected-(J6-Pad6)") (class "Default")
      (node (ref "J6") (pin "6") (pinfunction "6_6") (pintype "passive+no_connect"))
    )
    (net (code "117") (name "unconnected-(J6-Pad7)") (class "Default")
      (node (ref "J6") (pin "7") (pinfunction "7_7") (pintype "passive+no_connect"))
    )
    (net (code "118") (name "unconnected-(J6-Pad8)") (class "Default")
      (node (ref "J6") (pin "8") (pinfunction "8_8") (pintype "passive+no_connect"))
    )
    (net (code "119") (name "unconnected-(J6-Pad9)") (class "Default")
      (node (ref "J6") (pin "9") (pinfunction "9_9") (pintype "passive+no_connect"))
    )
    (net (code "120") (name "unconnected-(J6-Pad10)") (class "Default")
      (node (ref "J6") (pin "10") (pinfunction "10_10") (pintype "passive+no_connect"))
    )
    (net (code "121") (name "unconnected-(J6-Pad11)") (class "Default")
      (node (ref "J6") (pin "11") (pinfunction "11_11") (pintype "passive+no_connect"))
    )
    (net (code "122") (name "unconnected-(J6-Pad12)") (class "Default")
      (node (ref "J6") (pin "12") (pinfunction "12_12") (pintype "passive+no_connect"))
    )
    (net (code "123") (name "unconnected-(J6-Pad13)") (class "Default")
      (node (ref "J6") (pin "13") (pinfunction "13_13") (pintype "passive+no_connect"))
    )
    (net (code "124") (name "unconnected-(J6-Pad14)") (class "Default")
      (node (ref "J6") (pin "14") (pinfunction "14_14") (pintype "passive+no_connect"))
    )
    (net (code "125") (name "unconnected-(J6-Pad15)") (class "Default")
      (node (ref "J6") (pin "15") (pinfunction "15_15") (pintype "passive+no_connect"))
    )
    (net (code "126") (name "unconnected-(J6-Pad16)") (class "Default")
      (node (ref "J6") (pin "16") (pinfunction "16_16") (pintype "passive+no_connect"))
    )
    (net (code "127") (name "unconnected-(J6-Pad17)") (class "Default")
      (node (ref "J6") (pin "17") (pinfunction "17_17") (pintype "passive+no_connect"))
    )
    (net (code "128") (name "unconnected-(J6-Pad18)") (class "Default")
      (node (ref "J6") (pin "18") (pinfunction "18_18") (pintype "passive+no_connect"))
    )
    (net (code "129") (name "unconnected-(J6-Pad19)") (class "Default")
      (node (ref "J6") (pin "19") (pinfunction "19_19") (pintype "passive+no_connect"))
    )
    (net (code "130") (name "unconnected-(J6-Pad20)") (class "Default")
      (node (ref "J6") (pin "20") (pinfunction "20_20") (pintype "passive+no_connect"))
    )
    (net (code "131") (name "unconnected-(J6-Pad21)") (class "Default")
      (node (ref "J6") (pin "21") (pinfunction "21_21") (pintype "passive+no_connect"))
    )
    (net (code "132") (name "unconnected-(J6-Pad22)") (class "Default")
      (node (ref "J6") (pin "22") (pinfunction "22_22") (pintype "passive+no_connect"))
    )
    (net (code "133") (name "unconnected-(J6-Pad23)") (class "Default")
      (node (ref "J6") (pin "23") (pinfunction "23_23") (pintype "passive+no_connect"))
    )
    (net (code "134") (name "unconnected-(J6-Pad24)") (class "Default")
      (node (ref "J6") (pin "24") (pinfunction "24_24") (pintype "passive+no_connect"))
    )
    (net (code "135") (name "unconnected-(J6-Pad25)") (class "Default")
      (node (ref "J6") (pin "25") (pinfunction "25_25") (pintype "passive+no_connect"))
    )
    (net (code "136") (name "unconnected-(J6-Pad26)") (class "Default")
      (node (ref "J6") (pin "26") (pinfunction "26_26") (pintype "passive+no_connect"))
    )
    (net (code "137") (name "unconnected-(J6-Pad27)") (class "Default")
      (node (ref "J6") (pin "27") (pinfunction "27_27") (pintype "passive+no_connect"))
    )
    (net (code "138") (name "unconnected-(J6-Pad28)") (class "Default")
      (node (ref "J6") (pin "28") (pinfunction "28_28") (pintype "passive+no_connect"))
    )
    (net (code "139") (name "unconnected-(J6-Pad29)") (class "Default")
      (node (ref "J6") (pin "29") (pinfunction "29_29") (pintype "passive+no_connect"))
    )
    (net (code "140") (name "unconnected-(J6-Pad30)") (class "Default")
      (node (ref "J6") (pin "30") (pinfunction "30_30") (pintype "passive+no_connect"))
    )
    (net (code "141") (name "unconnected-(J6-Pad31)") (class "Default")
      (node (ref "J6") (pin "31") (pinfunction "31_31") (pintype "passive+no_connect"))
    )
    (net (code "142") (name "unconnected-(J6-Pad32)") (class "Default")
      (node (ref "J6") (pin "32") (pinfunction "32_32") (pintype "passive+no_connect"))
    )
    (net (code "143") (name "unconnected-(J6-Pad33)") (class "Default")
      (node (ref "J6") (pin "33") (pinfunction "33_33") (pintype "passive+no_connect"))
    )
    (net (code "144") (name "unconnected-(J6-Pad34)") (class "Default")
      (node (ref "J6") (pin "34") (pinfunction "34_34") (pintype "passive+no_connect"))
    )
    (net (code "145") (name "unconnected-(J6-Pad35)") (class "Default")
      (node (ref "J6") (pin "35") (pinfunction "35_35") (pintype "passive+no_connect"))
    )
    (net (code "146") (name "unconnected-(J6-Pad36)") (class "Default")
      (node (ref "J6") (pin "36") (pinfunction "36_36") (pintype "passive+no_connect"))
    )
    (net (code "147") (name "unconnected-(J6-Pad37)") (class "Default")
      (node (ref "J6") (pin "37") (pinfunction "37_37") (pintype "passive+no_connect"))
    )
    (net (code "148") (name "unconnected-(J6-Pad38)") (class "Default")
      (node (ref "J6") (pin "38") (pinfunction "38_38") (pintype "passive+no_connect"))
    )
    (net (code "149") (name "unconnected-(J6-Pad39)") (class "Default")
      (node (ref "J6") (pin "39") (pinfunction "39_39") (pintype "passive+no_connect"))
    )
    (net (code "150") (name "unconnected-(J6-Pad40)") (class "Default")
      (node (ref "J6") (pin "40") (pinfunction "40_40") (pintype "passive+no_connect"))
    )
    (net (code "151") (name "unconnected-(J6-Pad42)") (class "Default")
      (node (ref "J6") (pin "42") (pinfunction "42_42") (pintype "passive+no_connect"))
    )
    (net (code "152") (name "unconnected-(J6-Pad44)") (class "Default")
      (node (ref "J6") (pin "44") (pinfunction "44_44") (pintype "passive+no_connect"))
    )
    (net (code "153") (name "unconnected-(J6-Pad45)") (class "Default")
      (node (ref "J6") (pin "45") (pinfunction "45_45") (pintype "passive+no_connect"))
    )
    (net (code "154") (name "unconnected-(J6-Pad46)") (class "Default")
      (node (ref "J6") (pin "46") (pinfunction "46_46") (pintype "passive+no_connect"))
    )
    (net (code "155") (name "unconnected-(J7-Pad5)") (class "Default")
      (node (ref "J7") (pin "5") (pinfunction "5_5") (pintype "passive+no_connect"))
    )
    (net (code "156") (name "unconnected-(J10-Pad2)") (class "Default")
      (node (ref "J10") (pin "2") (pinfunction "2_2") (pintype "passive+no_connect"))
    )
    (net (code "157") (name "unconnected-(J10-Pad10)") (class "Default")
      (node (ref "J10") (pin "10") (pinfunction "10_10") (pintype "passive+no_connect"))
    )
    (net (code "158") (name "unconnected-(U9-N.C-Pad6)") (class "Default")
      (node (ref "U9") (pin "6") (pinfunction "N.C_6") (pintype "passive+no_connect"))
    )
    (net (code "159") (name "unconnected-(U9-N.C-Pad9)") (class "Default")
      (node (ref "U9") (pin "9") (pinfunction "N.C_9") (pintype "passive+no_connect"))
    )
    (net (code "160") (name "unconnected-(U10-NC-Pad1)") (class "Default")
      (node (ref "U10") (pin "1") (pinfunction "NC_1") (pintype "passive+no_connect"))
    )
    (net (code "161") (name "unconnected-(U10-NC-Pad8)") (class "Default")
      (node (ref "U10") (pin "8") (pinfunction "NC_8") (pintype "passive+no_connect"))
    )
    (net (code "162") (name "unconnected-(U10-NC-Pad13)") (class "Default")
      (node (ref "U10") (pin "13") (pinfunction "NC_13") (pintype "passive+no_connect"))
    )
  )
)
